# Qwiic_RF.net
KiCad netlist of a schematic drawn in EAGLE
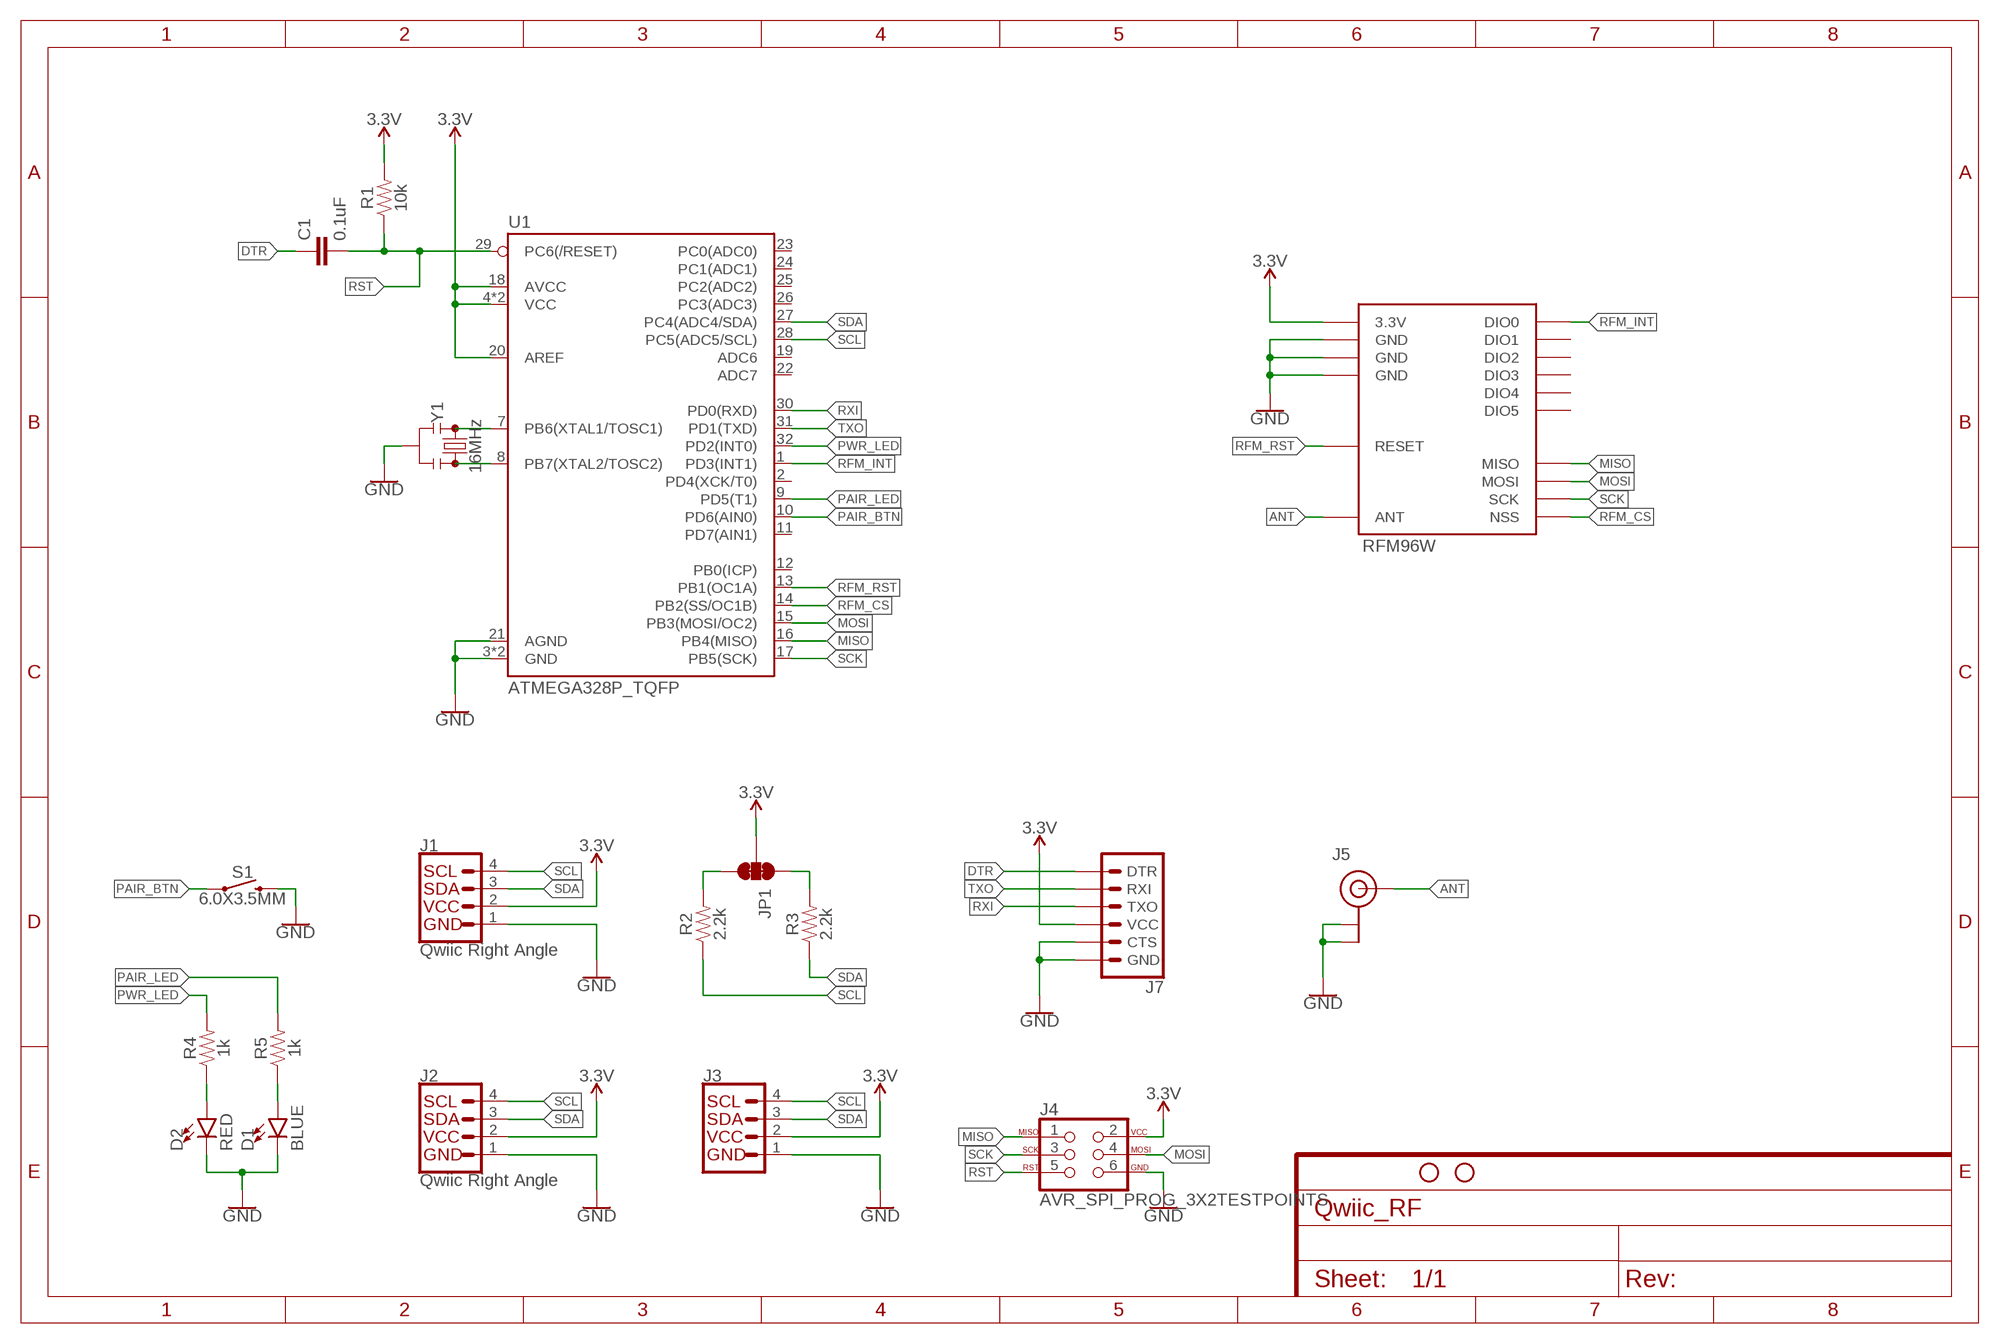
[diagram p0: schematic, sheet 1]

(export (version "E")
  (design (tool "Eeschema 10.0.6"))
  (components
    (comp (ref "C1")
      (value "0.1uF")
      (footprint "eagle-import:0603")
      (libsource (lib "eagle-import") (part "0.1UF-0603-25V-(+80/-20%)"))
    )
    (comp (ref "D1")
      (value "BLUE")
      (footprint "eagle-import:LED-0603")
      (libsource (lib "eagle-import") (part "LED-BLUE0603"))
    )
    (comp (ref "D2")
      (value "RED")
      (footprint "eagle-import:LED-0603")
      (libsource (lib "eagle-import") (part "LED-RED0603"))
    )
    (comp (ref "H1")
      (value "STAND-OFF")
      (footprint "eagle-import:STAND-OFF")
      (libsource (lib "eagle-import") (part "STAND-OFF"))
    )
    (comp (ref "H2")
      (value "STAND-OFF")
      (footprint "eagle-import:STAND-OFF")
      (libsource (lib "eagle-import") (part "STAND-OFF"))
    )
    (comp (ref "J1")
      (value "Qwiic Right Angle")
      (footprint "eagle-import:1X04_1MM_RA")
      (libsource (lib "eagle-import") (part "I2C_STANDARDQWIIC"))
    )
    (comp (ref "J2")
      (value "Qwiic Right Angle")
      (footprint "eagle-import:1X04_1MM_RA")
      (libsource (lib "eagle-import") (part "I2C_STANDARDQWIIC"))
    )
    (comp (ref "J3")
      (value "I2C_STANDARD")
      (footprint "eagle-import:1X04")
      (libsource (lib "eagle-import") (part "I2C_STANDARD"))
    )
    (comp (ref "J4")
      (value "AVR_SPI_PROG_3X2TESTPOINTS")
      (footprint "eagle-import:2X3_TEST_POINTS")
      (libsource (lib "eagle-import") (part "AVR_SPI_PROG_3X2TESTPOINTS"))
    )
    (comp (ref "J5")
      (value "U.FL")
      (footprint "eagle-import:U.FL")
      (libsource (lib "eagle-import") (part "U.FL"))
    )
    (comp (ref "J7")
      (value "6_PIN_SERIAL_TARGET")
      (footprint "eagle-import:1X06")
      (libsource (lib "eagle-import") (part "6_PIN_SERIAL_TARGET"))
    )
    (comp (ref "JP1")
      (value "JUMPER-SMT_3_2-NC_TRACE_SILK")
      (footprint "eagle-import:SMT-JUMPER_3_2-NC_TRACE_SILK")
      (libsource (lib "eagle-import") (part "JUMPER-SMT_3_2-NC_TRACE_SILK"))
    )
    (comp (ref "R1")
      (value "10k")
      (footprint "eagle-import:0603")
      (libsource (lib "eagle-import") (part "10KOHM-0603-1/10W-1%"))
    )
    (comp (ref "R2")
      (value "2.2k")
      (footprint "eagle-import:0603")
      (libsource (lib "eagle-import") (part "2.2KOHM-0603-1/10W-1%"))
    )
    (comp (ref "R3")
      (value "2.2k")
      (footprint "eagle-import:0603")
      (libsource (lib "eagle-import") (part "2.2KOHM-0603-1/10W-1%"))
    )
    (comp (ref "R4")
      (value "1k")
      (footprint "eagle-import:0603")
      (libsource (lib "eagle-import") (part "1KOHM-0603-1/10W-1%"))
    )
    (comp (ref "R5")
      (value "1k")
      (footprint "eagle-import:0603")
      (libsource (lib "eagle-import") (part "1KOHM-0603-1/10W-1%"))
    )
    (comp (ref "RFM96W")
      (value "RFM96W")
      (footprint "eagle-import:RFM95_96_97_98W")
      (libsource (lib "eagle-import") (part "RFM96W"))
    )
    (comp (ref "S1")
      (value "6.0X3.5MM")
      (footprint "eagle-import:TACTILE_SWITCH_SMD_6.0X3.5MM")
      (libsource (lib "eagle-import") (part "MOMENTARY-SWITCH-SPST-SMD-6.0X3.5MM"))
    )
    (comp (ref "U1")
      (value "ATMEGA328P_TQFP")
      (footprint "eagle-import:TQFP32-08")
      (libsource (lib "eagle-import") (part "ATMEGA328P_TQFP"))
    )
    (comp (ref "Y1")
      (value "16MHz")
      (footprint "eagle-import:RESONATOR-SMD-3.2X1.3")
      (libsource (lib "eagle-import") (part "RESONATOR-16MHZSMD_3.2X1.3"))
    )
  )
  (nets
    (net (code "1") (name "3.3V") (class "Default")
      (node (ref "J1") (pin "2") (pinfunction "2_2") (pintype "power_in"))
      (node (ref "J2") (pin "2") (pinfunction "2_2") (pintype "power_in"))
      (node (ref "J3") (pin "2") (pinfunction "2_2") (pintype "power_in"))
      (node (ref "J4") (pin "2") (pinfunction "2_2") (pintype "passive"))
      (node (ref "J7") (pin "4") (pinfunction "VCC_4") (pintype "passive"))
      (node (ref "JP1") (pin "2") (pinfunction "2_2") (pintype "passive"))
      (node (ref "R1") (pin "2") (pinfunction "2_2") (pintype "passive"))
      (node (ref "RFM96W") (pin "3.3V") (pinfunction "3.3V_3.3V") (pintype "bidirectional"))
      (node (ref "U1") (pin "18") (pinfunction "AVCC_18") (pintype "bidirectional"))
      (node (ref "U1") (pin "20") (pinfunction "AREF_20") (pintype "bidirectional"))
      (node (ref "U1") (pin "4") (pinfunction "VCC_4") (pintype "bidirectional"))
      (node (ref "U1") (pin "6") (pinfunction "VCC_6") (pintype "bidirectional"))
    )
    (net (code "2") (name "ANT") (class "Default")
      (node (ref "J5") (pin "FEED") (pinfunction "SIGNAL_FEED") (pintype "bidirectional"))
      (node (ref "RFM96W") (pin "ANT") (pinfunction "ANT_ANT") (pintype "bidirectional"))
    )
    (net (code "3") (name "DTR") (class "Default")
      (node (ref "C1") (pin "1") (pinfunction "1_1") (pintype "passive"))
      (node (ref "J7") (pin "1") (pinfunction "DTR_1") (pintype "passive"))
    )
    (net (code "4") (name "GND") (class "Default")
      (node (ref "D1") (pin "C") (pinfunction "C_C") (pintype "passive"))
      (node (ref "D2") (pin "C") (pinfunction "C_C") (pintype "passive"))
      (node (ref "J1") (pin "1") (pinfunction "1_1") (pintype "power_in"))
      (node (ref "J2") (pin "1") (pinfunction "1_1") (pintype "power_in"))
      (node (ref "J3") (pin "1") (pinfunction "1_1") (pintype "power_in"))
      (node (ref "J4") (pin "6") (pinfunction "6_6") (pintype "passive"))
      (node (ref "J5") (pin "1") (pinfunction "GND_1") (pintype "bidirectional"))
      (node (ref "J5") (pin "2") (pinfunction "GND_2") (pintype "bidirectional"))
      (node (ref "J7") (pin "5") (pinfunction "CTS_5") (pintype "passive"))
      (node (ref "J7") (pin "6") (pinfunction "GND_6") (pintype "passive"))
      (node (ref "RFM96W") (pin "GND@1") (pinfunction "GND_GND@1") (pintype "bidirectional"))
      (node (ref "RFM96W") (pin "GND@2") (pinfunction "GND_GND@2") (pintype "bidirectional"))
      (node (ref "RFM96W") (pin "GND@3") (pinfunction "GND_GND@3") (pintype "bidirectional"))
      (node (ref "S1") (pin "2") (pinfunction "2_2") (pintype "passive"))
      (node (ref "U1") (pin "21") (pinfunction "AGND_21") (pintype "bidirectional"))
      (node (ref "U1") (pin "3") (pinfunction "GND_3") (pintype "bidirectional"))
      (node (ref "U1") (pin "5") (pinfunction "GND_5") (pintype "bidirectional"))
      (node (ref "Y1") (pin "2") (pinfunction "2_2") (pintype "passive"))
    )
    (net (code "5") (name "MISO") (class "Default")
      (node (ref "J4") (pin "1") (pinfunction "1_1") (pintype "passive"))
      (node (ref "RFM96W") (pin "MISO") (pinfunction "MISO_MISO") (pintype "bidirectional"))
      (node (ref "U1") (pin "16") (pinfunction "PB4(MISO)_16") (pintype "bidirectional"))
    )
    (net (code "6") (name "MOSI") (class "Default")
      (node (ref "J4") (pin "4") (pinfunction "4_4") (pintype "passive"))
      (node (ref "RFM96W") (pin "MOSI") (pinfunction "MOSI_MOSI") (pintype "bidirectional"))
      (node (ref "U1") (pin "15") (pinfunction "PB3(MOSI/OC2)_15") (pintype "bidirectional"))
    )
    (net (code "7") (name "Net-(D1-PadA)") (class "Default")
      (node (ref "D1") (pin "A") (pinfunction "A_A") (pintype "passive"))
      (node (ref "R5") (pin "1") (pinfunction "1_1") (pintype "passive"))
    )
    (net (code "8") (name "Net-(D2-PadA)") (class "Default")
      (node (ref "D2") (pin "A") (pinfunction "A_A") (pintype "passive"))
      (node (ref "R4") (pin "1") (pinfunction "1_1") (pintype "passive"))
    )
    (net (code "9") (name "Net-(JP1-Pad1)") (class "Default")
      (node (ref "JP1") (pin "1") (pinfunction "1_1") (pintype "passive"))
      (node (ref "R3") (pin "2") (pinfunction "2_2") (pintype "passive"))
    )
    (net (code "10") (name "Net-(JP1-Pad3)") (class "Default")
      (node (ref "JP1") (pin "3") (pinfunction "3_3") (pintype "passive"))
      (node (ref "R2") (pin "2") (pinfunction "2_2") (pintype "passive"))
    )
    (net (code "11") (name "Net-(U1-PB6(XTAL1{slash}TOSC1))") (class "Default")
      (node (ref "U1") (pin "7") (pinfunction "PB6(XTAL1/TOSC1)_7") (pintype "bidirectional"))
      (node (ref "Y1") (pin "1") (pinfunction "1_1") (pintype "passive"))
    )
    (net (code "12") (name "Net-(U1-PB7(XTAL2{slash}TOSC2))") (class "Default")
      (node (ref "U1") (pin "8") (pinfunction "PB7(XTAL2/TOSC2)_8") (pintype "bidirectional"))
      (node (ref "Y1") (pin "3") (pinfunction "3_3") (pintype "passive"))
    )
    (net (code "13") (name "PAIR_BTN") (class "Default")
      (node (ref "S1") (pin "1") (pinfunction "1_1") (pintype "passive"))
      (node (ref "U1") (pin "10") (pinfunction "PD6(AIN0)_10") (pintype "bidirectional"))
    )
    (net (code "14") (name "PAIR_LED") (class "Default")
      (node (ref "R5") (pin "2") (pinfunction "2_2") (pintype "passive"))
      (node (ref "U1") (pin "9") (pinfunction "PD5(T1)_9") (pintype "bidirectional"))
    )
    (net (code "15") (name "PWR_LED") (class "Default")
      (node (ref "R4") (pin "2") (pinfunction "2_2") (pintype "passive"))
      (node (ref "U1") (pin "32") (pinfunction "PD2(INT0)_32") (pintype "bidirectional"))
    )
    (net (code "16") (name "RFM_CS") (class "Default")
      (node (ref "RFM96W") (pin "NSS") (pinfunction "NSS_NSS") (pintype "bidirectional"))
      (node (ref "U1") (pin "14") (pinfunction "PB2(SS/OC1B)_14") (pintype "bidirectional"))
    )
    (net (code "17") (name "RFM_INT") (class "Default")
      (node (ref "RFM96W") (pin "DIO0") (pinfunction "DIO0_DIO0") (pintype "bidirectional"))
      (node (ref "U1") (pin "1") (pinfunction "PD3(INT1)_1") (pintype "bidirectional"))
    )
    (net (code "18") (name "RFM_RST") (class "Default")
      (node (ref "RFM96W") (pin "RESET") (pinfunction "RESET_RESET") (pintype "bidirectional"))
      (node (ref "U1") (pin "13") (pinfunction "PB1(OC1A)_13") (pintype "bidirectional"))
    )
    (net (code "19") (name "RST") (class "Default")
      (node (ref "C1") (pin "2") (pinfunction "2_2") (pintype "passive"))
      (node (ref "J4") (pin "5") (pinfunction "5_5") (pintype "passive"))
      (node (ref "R1") (pin "1") (pinfunction "1_1") (pintype "passive"))
      (node (ref "U1") (pin "29") (pinfunction "PC6(/RESET)_29") (pintype "bidirectional"))
    )
    (net (code "20") (name "RXI") (class "Default")
      (node (ref "J7") (pin "3") (pinfunction "TXO_3") (pintype "passive"))
      (node (ref "U1") (pin "30") (pinfunction "PD0(RXD)_30") (pintype "bidirectional"))
    )
    (net (code "21") (name "SCK") (class "Default")
      (node (ref "J4") (pin "3") (pinfunction "3_3") (pintype "passive"))
      (node (ref "RFM96W") (pin "SCK") (pinfunction "SCK_SCK") (pintype "bidirectional"))
      (node (ref "U1") (pin "17") (pinfunction "PB5(SCK)_17") (pintype "bidirectional"))
    )
    (net (code "22") (name "SCL") (class "Default")
      (node (ref "J1") (pin "4") (pinfunction "4_4") (pintype "passive"))
      (node (ref "J2") (pin "4") (pinfunction "4_4") (pintype "passive"))
      (node (ref "J3") (pin "4") (pinfunction "4_4") (pintype "passive"))
      (node (ref "R2") (pin "1") (pinfunction "1_1") (pintype "passive"))
      (node (ref "U1") (pin "28") (pinfunction "PC5(ADC5/SCL)_28") (pintype "bidirectional"))
    )
    (net (code "23") (name "SDA") (class "Default")
      (node (ref "J1") (pin "3") (pinfunction "3_3") (pintype "passive"))
      (node (ref "J2") (pin "3") (pinfunction "3_3") (pintype "passive"))
      (node (ref "J3") (pin "3") (pinfunction "3_3") (pintype "passive"))
      (node (ref "R3") (pin "1") (pinfunction "1_1") (pintype "passive"))
      (node (ref "U1") (pin "27") (pinfunction "PC4(ADC4/SDA)_27") (pintype "bidirectional"))
    )
    (net (code "24") (name "TXO") (class "Default")
      (node (ref "J7") (pin "2") (pinfunction "RXI_2") (pintype "passive"))
      (node (ref "U1") (pin "31") (pinfunction "PD1(TXD)_31") (pintype "bidirectional"))
    )
    (net (code "25") (name "unconnected-(RFM96W-PadDIO1)") (class "Default")
      (node (ref "RFM96W") (pin "DIO1") (pinfunction "DIO1_DIO1") (pintype "bidirectional"))
    )
    (net (code "26") (name "unconnected-(RFM96W-PadDIO2)") (class "Default")
      (node (ref "RFM96W") (pin "DIO2") (pinfunction "DIO2_DIO2") (pintype "bidirectional"))
    )
    (net (code "27") (name "unconnected-(RFM96W-PadDIO3)") (class "Default")
      (node (ref "RFM96W") (pin "DIO3") (pinfunction "DIO3_DIO3") (pintype "bidirectional"))
    )
    (net (code "28") (name "unconnected-(RFM96W-PadDIO4)") (class "Default")
      (node (ref "RFM96W") (pin "DIO4") (pinfunction "DIO4_DIO4") (pintype "bidirectional"))
    )
    (net (code "29") (name "unconnected-(RFM96W-PadDIO5)") (class "Default")
      (node (ref "RFM96W") (pin "DIO5") (pinfunction "DIO5_DIO5") (pintype "bidirectional"))
    )
    (net (code "30") (name "unconnected-(U1-ADC6-Pad19)") (class "Default")
      (node (ref "U1") (pin "19") (pinfunction "ADC6_19") (pintype "bidirectional"))
    )
    (net (code "31") (name "unconnected-(U1-ADC7-Pad22)") (class "Default")
      (node (ref "U1") (pin "22") (pinfunction "ADC7_22") (pintype "bidirectional"))
    )
    (net (code "32") (name "unconnected-(U1-PB0(ICP)-Pad12)") (class "Default")
      (node (ref "U1") (pin "12") (pinfunction "PB0(ICP)_12") (pintype "bidirectional"))
    )
    (net (code "33") (name "unconnected-(U1-PC0(ADC0)-Pad23)") (class "Default")
      (node (ref "U1") (pin "23") (pinfunction "PC0(ADC0)_23") (pintype "bidirectional"))
    )
    (net (code "34") (name "unconnected-(U1-PC1(ADC1)-Pad24)") (class "Default")
      (node (ref "U1") (pin "24") (pinfunction "PC1(ADC1)_24") (pintype "bidirectional"))
    )
    (net (code "35") (name "unconnected-(U1-PC2(ADC2)-Pad25)") (class "Default")
      (node (ref "U1") (pin "25") (pinfunction "PC2(ADC2)_25") (pintype "bidirectional"))
    )
    (net (code "36") (name "unconnected-(U1-PC3(ADC3)-Pad26)") (class "Default")
      (node (ref "U1") (pin "26") (pinfunction "PC3(ADC3)_26") (pintype "bidirectional"))
    )
    (net (code "37") (name "unconnected-(U1-PD4(XCK{slash}T0)-Pad2)") (class "Default")
      (node (ref "U1") (pin "2") (pinfunction "PD4(XCK/T0)_2") (pintype "bidirectional"))
    )
    (net (code "38") (name "unconnected-(U1-PD7(AIN1)-Pad11)") (class "Default")
      (node (ref "U1") (pin "11") (pinfunction "PD7(AIN1)_11") (pintype "bidirectional"))
    )
  )
)
